# shield.net
KiCad netlist of a schematic drawn in EAGLE
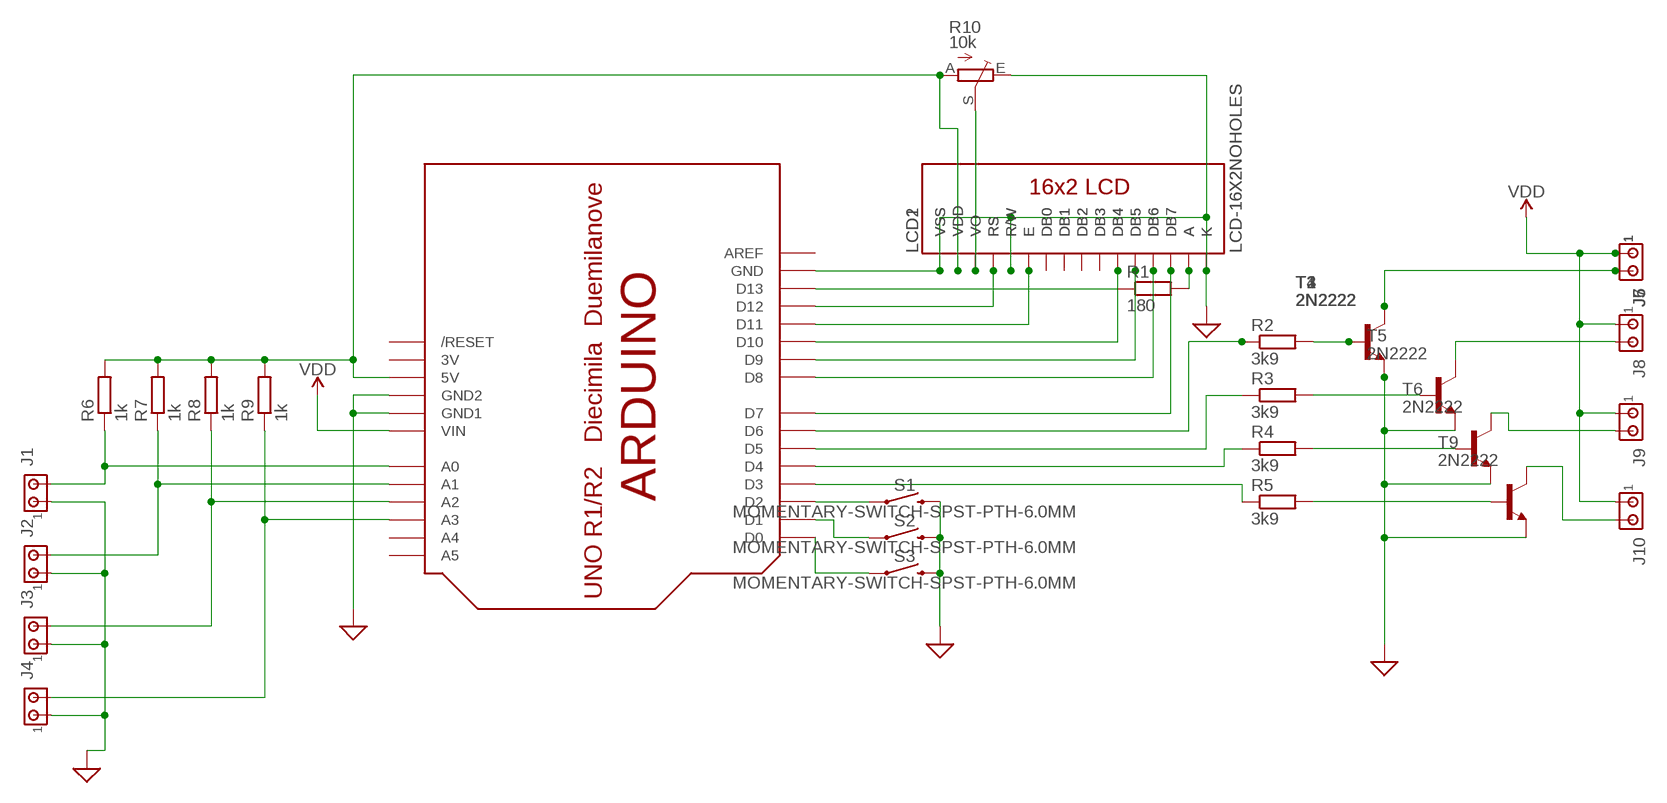
[diagram p0: schematic, sheet 1]

(export (version "E")
  (design (tool "Eeschema 10.0.6"))
  (components
    (comp (ref "J1")
      (value "MTA02-100")
      (footprint "eagle-import:10X02MTA")
      (libsource (lib "eagle-import") (part "MTA02-100"))
    )
    (comp (ref "J2")
      (value "MTA02-100")
      (footprint "eagle-import:10X02MTA")
      (libsource (lib "eagle-import") (part "MTA02-100"))
    )
    (comp (ref "J3")
      (value "MTA02-100")
      (footprint "eagle-import:10X02MTA")
      (libsource (lib "eagle-import") (part "MTA02-100"))
    )
    (comp (ref "J4")
      (value "MTA02-100")
      (footprint "eagle-import:10X02MTA")
      (libsource (lib "eagle-import") (part "MTA02-100"))
    )
    (comp (ref "J5")
      (value "MTA02-100")
      (footprint "eagle-import:10X02MTA")
      (libsource (lib "eagle-import") (part "MTA02-100"))
    )
    (comp (ref "J6")
      (value "MTA02-100")
      (footprint "eagle-import:10X02MTA")
      (libsource (lib "eagle-import") (part "MTA02-100"))
    )
    (comp (ref "J7")
      (value "MTA02-100")
      (footprint "eagle-import:10X02MTA")
      (libsource (lib "eagle-import") (part "MTA02-100"))
    )
    (comp (ref "J8")
      (value "MTA02-100")
      (footprint "eagle-import:10X02MTA")
      (libsource (lib "eagle-import") (part "MTA02-100"))
    )
    (comp (ref "J9")
      (value "MTA02-100")
      (footprint "eagle-import:10X02MTA")
      (libsource (lib "eagle-import") (part "MTA02-100"))
    )
    (comp (ref "J10")
      (value "MTA02-100")
      (footprint "eagle-import:10X02MTA")
      (libsource (lib "eagle-import") (part "MTA02-100"))
    )
    (comp (ref "LCD1")
      (value "LCD-16X2NOHOLES")
      (footprint "eagle-import:LCD-16X2_NOHOLESNOSILK")
      (libsource (lib "eagle-import") (part "LCD-16X2NOHOLES"))
    )
    (comp (ref "LCD2")
      (value "LCD-16X2NOHOLES")
      (footprint "eagle-import:LCD-16X2_NOHOLESNOSILK")
      (libsource (lib "eagle-import") (part "LCD-16X2NOHOLES"))
    )
    (comp (ref "R1")
      (value "180")
      (footprint "eagle-import:0207_10")
      (libsource (lib "eagle-import") (part "R-EU_0207/10"))
    )
    (comp (ref "R2")
      (value "3k9")
      (footprint "eagle-import:0207_10")
      (libsource (lib "eagle-import") (part "R-EU_0207/10"))
    )
    (comp (ref "R3")
      (value "3k9")
      (footprint "eagle-import:0207_10")
      (libsource (lib "eagle-import") (part "R-EU_0207/10"))
    )
    (comp (ref "R4")
      (value "3k9")
      (footprint "eagle-import:0207_10")
      (libsource (lib "eagle-import") (part "R-EU_0207/10"))
    )
    (comp (ref "R5")
      (value "3k9")
      (footprint "eagle-import:0207_10")
      (libsource (lib "eagle-import") (part "R-EU_0207/10"))
    )
    (comp (ref "R6")
      (value "1k")
      (footprint "eagle-import:0207_10")
      (libsource (lib "eagle-import") (part "R-EU_0207/10"))
    )
    (comp (ref "R7")
      (value "1k")
      (footprint "eagle-import:0207_10")
      (libsource (lib "eagle-import") (part "R-EU_0207/10"))
    )
    (comp (ref "R8")
      (value "1k")
      (footprint "eagle-import:0207_10")
      (libsource (lib "eagle-import") (part "R-EU_0207/10"))
    )
    (comp (ref "R9")
      (value "1k")
      (footprint "eagle-import:0207_10")
      (libsource (lib "eagle-import") (part "R-EU_0207/10"))
    )
    (comp (ref "R10")
      (value "10k")
      (footprint "eagle-import:B25P")
      (libsource (lib "eagle-import") (part "TRIM_EU-B25P"))
    )
    (comp (ref "S1")
      (value "MOMENTARY-SWITCH-SPST-PTH-6.0MM")
      (footprint "eagle-import:TACTILE_SWITCH_PTH_6.0MM")
      (libsource (lib "eagle-import") (part "MOMENTARY-SWITCH-SPST-PTH-6.0MM"))
    )
    (comp (ref "S2")
      (value "MOMENTARY-SWITCH-SPST-PTH-6.0MM")
      (footprint "eagle-import:TACTILE_SWITCH_PTH_6.0MM")
      (libsource (lib "eagle-import") (part "MOMENTARY-SWITCH-SPST-PTH-6.0MM"))
    )
    (comp (ref "S3")
      (value "MOMENTARY-SWITCH-SPST-PTH-6.0MM")
      (footprint "eagle-import:TACTILE_SWITCH_PTH_6.0MM")
      (libsource (lib "eagle-import") (part "MOMENTARY-SWITCH-SPST-PTH-6.0MM"))
    )
    (comp (ref "T1")
      (value "2N2222")
      (footprint "eagle-import:TO92-EBC-OVAL")
      (libsource (lib "eagle-import") (part "2N2222"))
    )
    (comp (ref "T2")
      (value "2N2222")
      (footprint "eagle-import:TO92-EBC-OVAL")
      (libsource (lib "eagle-import") (part "2N2222"))
    )
    (comp (ref "T3")
      (value "2N2222")
      (footprint "eagle-import:TO92-EBC-OVAL")
      (libsource (lib "eagle-import") (part "2N2222"))
    )
    (comp (ref "T4")
      (value "2N2222")
      (footprint "eagle-import:TO92-EBC-OVAL")
      (libsource (lib "eagle-import") (part "2N2222"))
    )
    (comp (ref "T5")
      (value "2N2222")
      (footprint "eagle-import:TO92-EBC-OVAL")
      (libsource (lib "eagle-import") (part "2N2222"))
    )
    (comp (ref "T6")
      (value "2N2222")
      (footprint "eagle-import:TO92-EBC-OVAL")
      (libsource (lib "eagle-import") (part "2N2222"))
    )
    (comp (ref "T9")
      (value "2N2222")
      (footprint "eagle-import:TO92-EBC-OVAL")
      (libsource (lib "eagle-import") (part "2N2222"))
    )
    (comp (ref "U$1")
      (value "ARDUINO-NOHOLE")
      (footprint "eagle-import:ARDUINO-NOHOLE")
      (libsource (lib "eagle-import") (part "ARDUINO-NOHOLE"))
    )
  )
  (nets
    (net (code "1") (name "/3V") (class "Default")
      (node (ref "U$1") (pin "3V") (pinfunction "3V_3V") (pintype "power_in"))
    )
    (net (code "2") (name "Net-(J1-Pad2)") (class "Default")
      (node (ref "J1") (pin "2") (pinfunction "2_2") (pintype "passive"))
      (node (ref "R6") (pin "1") (pinfunction "1_1") (pintype "passive"))
      (node (ref "U$1") (pin "A0") (pinfunction "A0_A0") (pintype "bidirectional"))
    )
    (net (code "3") (name "Net-(J2-Pad2)") (class "Default")
      (node (ref "J2") (pin "2") (pinfunction "2_2") (pintype "passive"))
      (node (ref "R7") (pin "1") (pinfunction "1_1") (pintype "passive"))
      (node (ref "U$1") (pin "A1") (pinfunction "A1_A1") (pintype "bidirectional"))
    )
    (net (code "4") (name "Net-(J3-Pad2)") (class "Default")
      (node (ref "J3") (pin "2") (pinfunction "2_2") (pintype "passive"))
      (node (ref "R8") (pin "1") (pinfunction "1_1") (pintype "passive"))
      (node (ref "U$1") (pin "A2") (pinfunction "A2_A2") (pintype "bidirectional"))
    )
    (net (code "5") (name "Net-(J4-Pad2)") (class "Default")
      (node (ref "J4") (pin "2") (pinfunction "2_2") (pintype "passive"))
      (node (ref "R9") (pin "1") (pinfunction "1_1") (pintype "passive"))
      (node (ref "U$1") (pin "A3") (pinfunction "A3_A3") (pintype "bidirectional"))
    )
    (net (code "6") (name "Net-(J5-Pad2)") (class "Default")
      (node (ref "J5") (pin "2") (pinfunction "2_2") (pintype "passive"))
      (node (ref "J6") (pin "2") (pinfunction "2_2") (pintype "passive"))
      (node (ref "J7") (pin "2") (pinfunction "2_2") (pintype "passive"))
      (node (ref "T1") (pin "C") (pinfunction "C_C") (pintype "passive"))
      (node (ref "T2") (pin "C") (pinfunction "C_C") (pintype "passive"))
      (node (ref "T3") (pin "C") (pinfunction "C_C") (pintype "passive"))
      (node (ref "T4") (pin "C") (pinfunction "C_C") (pintype "passive"))
    )
    (net (code "7") (name "Net-(J8-Pad2)") (class "Default")
      (node (ref "J8") (pin "2") (pinfunction "2_2") (pintype "passive"))
      (node (ref "T5") (pin "C") (pinfunction "C_C") (pintype "passive"))
    )
    (net (code "8") (name "Net-(J9-Pad2)") (class "Default")
      (node (ref "J9") (pin "2") (pinfunction "2_2") (pintype "passive"))
      (node (ref "T6") (pin "C") (pinfunction "C_C") (pintype "passive"))
    )
    (net (code "9") (name "Net-(J10-Pad2)") (class "Default")
      (node (ref "J10") (pin "2") (pinfunction "2_2") (pintype "passive"))
      (node (ref "T9") (pin "C") (pinfunction "C_C") (pintype "passive"))
    )
    (net (code "10") (name "Net-(LCD1-A)") (class "Default")
      (node (ref "LCD1") (pin "15") (pinfunction "A_15") (pintype "power_in"))
      (node (ref "LCD2") (pin "15") (pinfunction "A_15") (pintype "power_in"))
      (node (ref "R1") (pin "2") (pinfunction "2_2") (pintype "passive"))
    )
    (net (code "11") (name "Net-(LCD1-DB0)") (class "Default")
      (node (ref "LCD1") (pin "7") (pinfunction "DB0_7") (pintype "bidirectional"))
      (node (ref "LCD2") (pin "7") (pinfunction "DB0_7") (pintype "bidirectional"))
    )
    (net (code "12") (name "Net-(LCD1-DB1)") (class "Default")
      (node (ref "LCD1") (pin "8") (pinfunction "DB1_8") (pintype "bidirectional"))
      (node (ref "LCD2") (pin "8") (pinfunction "DB1_8") (pintype "bidirectional"))
    )
    (net (code "13") (name "Net-(LCD1-DB2)") (class "Default")
      (node (ref "LCD1") (pin "9") (pinfunction "DB2_9") (pintype "bidirectional"))
      (node (ref "LCD2") (pin "9") (pinfunction "DB2_9") (pintype "bidirectional"))
    )
    (net (code "14") (name "Net-(LCD1-DB3)") (class "Default")
      (node (ref "LCD1") (pin "10") (pinfunction "DB3_10") (pintype "bidirectional"))
      (node (ref "LCD2") (pin "10") (pinfunction "DB3_10") (pintype "bidirectional"))
    )
    (net (code "15") (name "Net-(LCD1-DB4)") (class "Default")
      (node (ref "LCD1") (pin "11") (pinfunction "DB4_11") (pintype "bidirectional"))
      (node (ref "LCD2") (pin "11") (pinfunction "DB4_11") (pintype "bidirectional"))
      (node (ref "U$1") (pin "D10") (pinfunction "D10_D10") (pintype "bidirectional"))
    )
    (net (code "16") (name "Net-(LCD1-DB5)") (class "Default")
      (node (ref "LCD1") (pin "12") (pinfunction "DB5_12") (pintype "bidirectional"))
      (node (ref "LCD2") (pin "12") (pinfunction "DB5_12") (pintype "bidirectional"))
      (node (ref "U$1") (pin "D9") (pinfunction "D9_D9") (pintype "bidirectional"))
    )
    (net (code "17") (name "Net-(LCD1-DB6)") (class "Default")
      (node (ref "LCD1") (pin "13") (pinfunction "DB6_13") (pintype "bidirectional"))
      (node (ref "LCD2") (pin "13") (pinfunction "DB6_13") (pintype "bidirectional"))
      (node (ref "U$1") (pin "D8") (pinfunction "D8_D8") (pintype "bidirectional"))
    )
    (net (code "18") (name "Net-(LCD1-DB7)") (class "Default")
      (node (ref "LCD1") (pin "14") (pinfunction "DB7_14") (pintype "bidirectional"))
      (node (ref "LCD2") (pin "14") (pinfunction "DB7_14") (pintype "bidirectional"))
      (node (ref "U$1") (pin "D7") (pinfunction "D7_D7") (pintype "bidirectional"))
    )
    (net (code "19") (name "Net-(LCD1-E)") (class "Default")
      (node (ref "LCD1") (pin "6") (pinfunction "E_6") (pintype "input"))
      (node (ref "LCD2") (pin "6") (pinfunction "E_6") (pintype "input"))
      (node (ref "U$1") (pin "D11") (pinfunction "D11_D11") (pintype "bidirectional"))
    )
    (net (code "20") (name "Net-(LCD1-RS)") (class "Default")
      (node (ref "LCD1") (pin "4") (pinfunction "RS_4") (pintype "input"))
      (node (ref "LCD2") (pin "4") (pinfunction "RS_4") (pintype "input"))
      (node (ref "U$1") (pin "D12") (pinfunction "D12_D12") (pintype "bidirectional"))
    )
    (net (code "21") (name "Net-(LCD1-VDD)") (class "Default")
      (node (ref "LCD1") (pin "2") (pinfunction "VDD_2") (pintype "power_in"))
      (node (ref "LCD2") (pin "2") (pinfunction "VDD_2") (pintype "power_in"))
      (node (ref "R10") (pin "A") (pinfunction "A_A") (pintype "passive"))
      (node (ref "R6") (pin "2") (pinfunction "2_2") (pintype "passive"))
      (node (ref "R7") (pin "2") (pinfunction "2_2") (pintype "passive"))
      (node (ref "R8") (pin "2") (pinfunction "2_2") (pintype "passive"))
      (node (ref "R9") (pin "2") (pinfunction "2_2") (pintype "passive"))
      (node (ref "U$1") (pin "5V") (pinfunction "5V_5V") (pintype "power_in"))
    )
    (net (code "22") (name "Net-(LCD1-VO)") (class "Default")
      (node (ref "LCD1") (pin "3") (pinfunction "VO_3") (pintype "bidirectional"))
      (node (ref "LCD2") (pin "3") (pinfunction "VO_3") (pintype "bidirectional"))
      (node (ref "R10") (pin "S") (pinfunction "S_S") (pintype "passive"))
    )
    (net (code "23") (name "Net-(R1-Pad1)") (class "Default")
      (node (ref "R1") (pin "1") (pinfunction "1_1") (pintype "passive"))
      (node (ref "U$1") (pin "D13") (pinfunction "D13_D13") (pintype "bidirectional"))
    )
    (net (code "24") (name "Net-(R2-Pad1)") (class "Default")
      (node (ref "R2") (pin "1") (pinfunction "1_1") (pintype "passive"))
      (node (ref "U$1") (pin "D6") (pinfunction "D6_D6") (pintype "bidirectional"))
    )
    (net (code "25") (name "Net-(R2-Pad2)") (class "Default")
      (node (ref "R2") (pin "2") (pinfunction "2_2") (pintype "passive"))
      (node (ref "T1") (pin "B") (pinfunction "B_B") (pintype "passive"))
      (node (ref "T2") (pin "B") (pinfunction "B_B") (pintype "passive"))
      (node (ref "T3") (pin "B") (pinfunction "B_B") (pintype "passive"))
      (node (ref "T4") (pin "B") (pinfunction "B_B") (pintype "passive"))
    )
    (net (code "26") (name "Net-(R3-Pad1)") (class "Default")
      (node (ref "R3") (pin "1") (pinfunction "1_1") (pintype "passive"))
      (node (ref "U$1") (pin "D5") (pinfunction "D5_D5") (pintype "bidirectional"))
    )
    (net (code "27") (name "Net-(R3-Pad2)") (class "Default")
      (node (ref "R3") (pin "2") (pinfunction "2_2") (pintype "passive"))
      (node (ref "T5") (pin "B") (pinfunction "B_B") (pintype "passive"))
    )
    (net (code "28") (name "Net-(R4-Pad1)") (class "Default")
      (node (ref "R4") (pin "1") (pinfunction "1_1") (pintype "passive"))
      (node (ref "U$1") (pin "D4") (pinfunction "D4_D4") (pintype "bidirectional"))
    )
    (net (code "29") (name "Net-(R4-Pad2)") (class "Default")
      (node (ref "R4") (pin "2") (pinfunction "2_2") (pintype "passive"))
      (node (ref "T6") (pin "B") (pinfunction "B_B") (pintype "passive"))
    )
    (net (code "30") (name "Net-(R5-Pad1)") (class "Default")
      (node (ref "R5") (pin "1") (pinfunction "1_1") (pintype "passive"))
      (node (ref "U$1") (pin "D3") (pinfunction "D3_D3") (pintype "bidirectional"))
    )
    (net (code "31") (name "Net-(R5-Pad2)") (class "Default")
      (node (ref "R5") (pin "2") (pinfunction "2_2") (pintype "passive"))
      (node (ref "T9") (pin "B") (pinfunction "B_B") (pintype "passive"))
    )
    (net (code "32") (name "Net-(S1-Pad1)") (class "Default")
      (node (ref "S1") (pin "1") (pinfunction "1_1") (pintype "passive"))
      (node (ref "U$1") (pin "D2") (pinfunction "D2_D2") (pintype "bidirectional"))
    )
    (net (code "33") (name "Net-(S2-Pad1)") (class "Default")
      (node (ref "S2") (pin "1") (pinfunction "1_1") (pintype "passive"))
      (node (ref "U$1") (pin "D1") (pinfunction "D1_D1") (pintype "bidirectional"))
    )
    (net (code "34") (name "Net-(S3-Pad1)") (class "Default")
      (node (ref "S3") (pin "1") (pinfunction "1_1") (pintype "passive"))
      (node (ref "U$1") (pin "D0") (pinfunction "D0_D0") (pintype "bidirectional"))
    )
    (net (code "35") (name "SUP") (class "Default")
      (node (ref "J1") (pin "1") (pinfunction "1_1") (pintype "passive"))
      (node (ref "J2") (pin "1") (pinfunction "1_1") (pintype "passive"))
      (node (ref "J3") (pin "1") (pinfunction "1_1") (pintype "passive"))
      (node (ref "J4") (pin "1") (pinfunction "1_1") (pintype "passive"))
      (node (ref "LCD1") (pin "1") (pinfunction "VSS_1") (pintype "power_in"))
      (node (ref "LCD1") (pin "16") (pinfunction "K_16") (pintype "power_in"))
      (node (ref "LCD1") (pin "5") (pinfunction "R/W_5") (pintype "input"))
      (node (ref "LCD2") (pin "1") (pinfunction "VSS_1") (pintype "power_in"))
      (node (ref "LCD2") (pin "16") (pinfunction "K_16") (pintype "power_in"))
      (node (ref "LCD2") (pin "5") (pinfunction "R/W_5") (pintype "input"))
      (node (ref "R10") (pin "E") (pinfunction "E_E") (pintype "passive"))
      (node (ref "S1") (pin "3") (pinfunction "2_3") (pintype "passive"))
      (node (ref "S2") (pin "3") (pinfunction "2_3") (pintype "passive"))
      (node (ref "S3") (pin "3") (pinfunction "2_3") (pintype "passive"))
      (node (ref "T1") (pin "E") (pinfunction "E_E") (pintype "passive"))
      (node (ref "T2") (pin "E") (pinfunction "E_E") (pintype "passive"))
      (node (ref "T3") (pin "E") (pinfunction "E_E") (pintype "passive"))
      (node (ref "T4") (pin "E") (pinfunction "E_E") (pintype "passive"))
      (node (ref "T5") (pin "E") (pinfunction "E_E") (pintype "passive"))
      (node (ref "T6") (pin "E") (pinfunction "E_E") (pintype "passive"))
      (node (ref "T9") (pin "E") (pinfunction "E_E") (pintype "passive"))
      (node (ref "U$1") (pin "GND") (pinfunction "GND_GND") (pintype "power_in"))
      (node (ref "U$1") (pin "GND1") (pinfunction "GND1_GND1") (pintype "power_in"))
      (node (ref "U$1") (pin "GND2") (pinfunction "GND2_GND2") (pintype "power_in"))
    )
    (net (code "36") (name "VDD") (class "Default")
      (node (ref "J10") (pin "1") (pinfunction "1_1") (pintype "passive"))
      (node (ref "J5") (pin "1") (pinfunction "1_1") (pintype "passive"))
      (node (ref "J6") (pin "1") (pinfunction "1_1") (pintype "passive"))
      (node (ref "J7") (pin "1") (pinfunction "1_1") (pintype "passive"))
      (node (ref "J8") (pin "1") (pinfunction "1_1") (pintype "passive"))
      (node (ref "J9") (pin "1") (pinfunction "1_1") (pintype "passive"))
      (node (ref "U$1") (pin "VIN") (pinfunction "VIN_VIN") (pintype "power_in"))
    )
    (net (code "37") (name "unconnected-(U$1-PadA4)") (class "Default")
      (node (ref "U$1") (pin "A4") (pinfunction "A4_A4") (pintype "bidirectional"))
    )
    (net (code "38") (name "unconnected-(U$1-PadA5)") (class "Default")
      (node (ref "U$1") (pin "A5") (pinfunction "A5_A5") (pintype "bidirectional"))
    )
    (net (code "39") (name "unconnected-(U$1-PadAREF)") (class "Default")
      (node (ref "U$1") (pin "AREF") (pinfunction "AREF_AREF") (pintype "bidirectional"))
    )
    (net (code "40") (name "unconnected-(U$1-{slash}RESET-PadRESET)") (class "Default")
      (node (ref "U$1") (pin "RESET") (pinfunction "/RESET_RESET") (pintype "bidirectional"))
    )
  )
)
